# secondboard.net
KiCad netlist of a schematic drawn in EAGLE
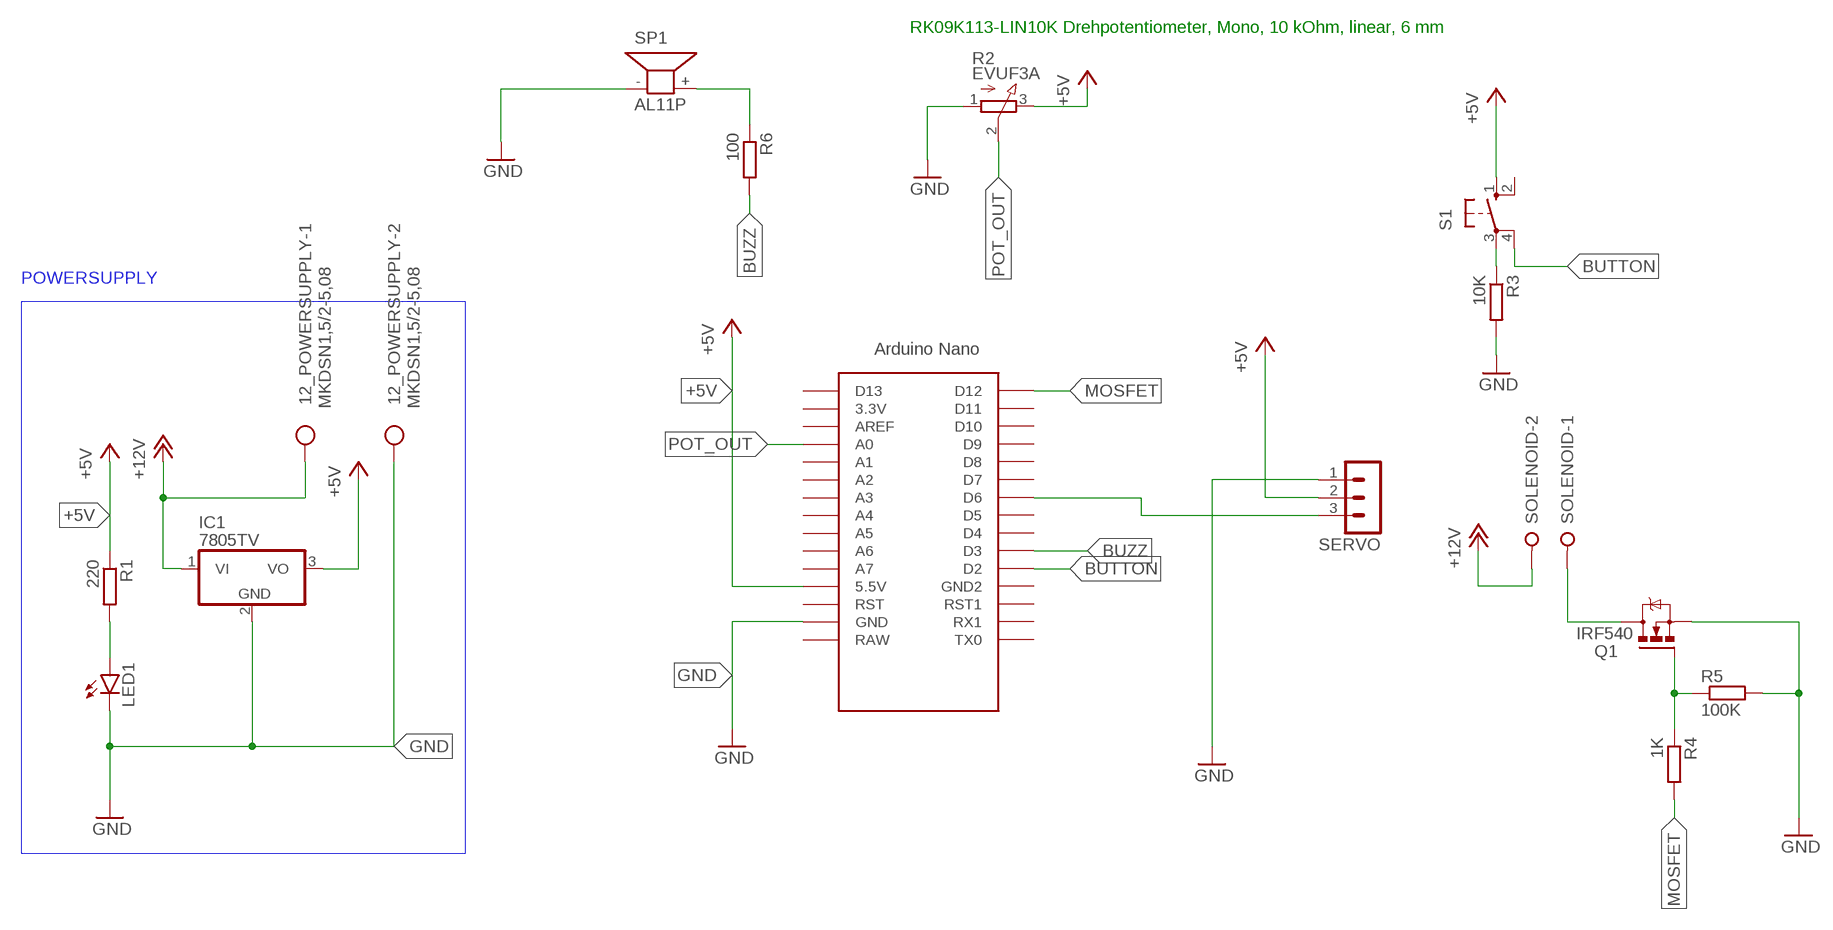
[diagram p0: schematic, sheet 1]

(export (version "E")
  (design (tool "Eeschema 10.0.6"))
  (components
    (comp (ref "12_POWERSUPPLY")
      (value "MKDSN1,5/2-5,08")
      (footprint "eagle-import:MKDSN1,5_2-5,08")
      (libsource (lib "eagle-import") (part "MKDSN1,5/2-5,08"))
    )
    (comp (ref "IC1")
      (value "7805TV")
      (footprint "eagle-import:TO220V")
      (libsource (lib "eagle-import") (part "78TV05"))
    )
    (comp (ref "LED1")
      (value "LED3MM")
      (footprint "eagle-import:LED3MM")
      (libsource (lib "eagle-import") (part "LED3MM"))
    )
    (comp (ref "Q1")
      (value "IRF540")
      (footprint "eagle-import:TO220BV")
      (libsource (lib "eagle-import") (part "IRF540"))
    )
    (comp (ref "R1")
      (value "220")
      (footprint "eagle-import:R0805")
      (libsource (lib "eagle-import") (part "R-EU_R0805"))
    )
    (comp (ref "R2")
      (value "EVUF3A")
      (footprint "eagle-import:EVUF")
      (libsource (lib "eagle-import") (part "EVUAF3"))
    )
    (comp (ref "R3")
      (value "10K")
      (footprint "eagle-import:R0805")
      (libsource (lib "eagle-import") (part "R-EU_R0805"))
    )
    (comp (ref "R4")
      (value "1K")
      (footprint "eagle-import:R0805")
      (libsource (lib "eagle-import") (part "R-EU_R0805"))
    )
    (comp (ref "R5")
      (value "100K")
      (footprint "eagle-import:R0805")
      (libsource (lib "eagle-import") (part "R-EU_R0805"))
    )
    (comp (ref "R6")
      (value "100")
      (footprint "eagle-import:R0805")
      (libsource (lib "eagle-import") (part "R-EU_R0805"))
    )
    (comp (ref "S1")
      (value "10-XX")
      (footprint "eagle-import:B3F-10XX")
      (fields (field (name "MPN") "B3F-1000"))
      (libsource (lib "eagle-import") (part "10-XX"))
    )
    (comp (ref "SERVO")
      (value "MA03-1")
      (footprint "eagle-import:MA03-1")
      (libsource (lib "eagle-import") (part "MA03-1"))
    )
    (comp (ref "SOLENOID")
      (value "W237-02P")
      (footprint "eagle-import:W237-132")
      (libsource (lib "eagle-import") (part "W237-02P"))
    )
    (comp (ref "SP1")
      (value "AL11P")
      (footprint "eagle-import:AL11P")
      (libsource (lib "eagle-import") (part "AL11P"))
    )
    (comp (ref "U$1")
      (value "NANO")
      (footprint "eagle-import:NANO")
      (libsource (lib "eagle-import") (part "NANO"))
    )
  )
  (nets
    (net (code "1") (name "+5V") (class "Default")
      (node (ref "IC1") (pin "3") (pinfunction "VO_3") (pintype "passive"))
      (node (ref "R1") (pin "1") (pinfunction "1_1") (pintype "passive"))
      (node (ref "R2") (pin "3") (pinfunction "E_3") (pintype "passive"))
      (node (ref "S1") (pin "1") (pinfunction "S_1") (pintype "passive"))
      (node (ref "SERVO") (pin "2") (pinfunction "2_2") (pintype "passive"))
      (node (ref "U$1") (pin "5V") (pinfunction "5.5V_5V") (pintype "bidirectional"))
    )
    (net (code "2") (name "+12V") (class "Default")
      (node (ref "12_POWERSUPPLY") (pin "1") (pinfunction "KL_1") (pintype "passive"))
      (node (ref "IC1") (pin "1") (pinfunction "VI_1") (pintype "input"))
      (node (ref "SOLENOID") (pin "2") (pinfunction "KL_2") (pintype "passive"))
    )
    (net (code "3") (name "BUTTON") (class "Default")
      (node (ref "S1") (pin "4") (pinfunction "P1_4") (pintype "passive"))
      (node (ref "U$1") (pin "D2") (pinfunction "D2_D2") (pintype "bidirectional"))
    )
    (net (code "4") (name "BUZZ") (class "Default")
      (node (ref "R6") (pin "2") (pinfunction "2_2") (pintype "passive"))
      (node (ref "U$1") (pin "D3") (pinfunction "D3_D3") (pintype "bidirectional"))
    )
    (net (code "5") (name "GND") (class "Default")
      (node (ref "12_POWERSUPPLY") (pin "2") (pinfunction "KL_2") (pintype "passive"))
      (node (ref "IC1") (pin "2") (pinfunction "GND_2") (pintype "passive"))
      (node (ref "LED1") (pin "K") (pinfunction "C_K") (pintype "passive"))
      (node (ref "Q1") (pin "S") (pinfunction "S_S") (pintype "passive"))
      (node (ref "R2") (pin "1") (pinfunction "A_1") (pintype "passive"))
      (node (ref "R3") (pin "2") (pinfunction "2_2") (pintype "passive"))
      (node (ref "R5") (pin "2") (pinfunction "2_2") (pintype "passive"))
      (node (ref "SERVO") (pin "1") (pinfunction "1_1") (pintype "passive"))
      (node (ref "SP1") (pin "-") (pinfunction "1_-") (pintype "passive"))
      (node (ref "U$1") (pin "GND") (pinfunction "GND_GND") (pintype "bidirectional"))
    )
    (net (code "6") (name "MOSFET") (class "Default")
      (node (ref "R4") (pin "2") (pinfunction "2_2") (pintype "passive"))
      (node (ref "U$1") (pin "D12") (pinfunction "D12_D12") (pintype "bidirectional"))
    )
    (net (code "7") (name "Net-(LED1-PadA)") (class "Default")
      (node (ref "LED1") (pin "A") (pinfunction "A_A") (pintype "passive"))
      (node (ref "R1") (pin "2") (pinfunction "2_2") (pintype "passive"))
    )
    (net (code "8") (name "Net-(Q1-PadG)") (class "Default")
      (node (ref "Q1") (pin "G") (pinfunction "G_G") (pintype "passive"))
      (node (ref "R4") (pin "1") (pinfunction "1_1") (pintype "passive"))
      (node (ref "R5") (pin "1") (pinfunction "1_1") (pintype "passive"))
    )
    (net (code "9") (name "Net-(S1-P)") (class "Default")
      (node (ref "R3") (pin "1") (pinfunction "1_1") (pintype "passive"))
      (node (ref "S1") (pin "3") (pinfunction "P_3") (pintype "passive"))
    )
    (net (code "10") (name "Net-(SERVO-Pad3)") (class "Default")
      (node (ref "SERVO") (pin "3") (pinfunction "3_3") (pintype "passive"))
      (node (ref "U$1") (pin "D6") (pinfunction "D6_D6") (pintype "bidirectional"))
    )
    (net (code "11") (name "Net-(SOLENOIDA-KL)") (class "Default")
      (node (ref "Q1") (pin "D") (pinfunction "D_D") (pintype "passive"))
      (node (ref "SOLENOID") (pin "1") (pinfunction "KL_1") (pintype "passive"))
    )
    (net (code "12") (name "Net-(SP1-2)") (class "Default")
      (node (ref "R6") (pin "1") (pinfunction "1_1") (pintype "passive"))
      (node (ref "SP1") (pin "+") (pinfunction "2_+") (pintype "passive"))
    )
    (net (code "13") (name "POT_OUT") (class "Default")
      (node (ref "R2") (pin "2") (pinfunction "S_2") (pintype "passive"))
      (node (ref "U$1") (pin "A0") (pinfunction "A0_A0") (pintype "bidirectional"))
    )
    (net (code "14") (name "unconnected-(S1-S1-Pad2)") (class "Default")
      (node (ref "S1") (pin "2") (pinfunction "S1_2") (pintype "passive"))
    )
    (net (code "15") (name "unconnected-(U$1-GND2-PadGND1)") (class "Default")
      (node (ref "U$1") (pin "GND1") (pinfunction "GND2_GND1") (pintype "bidirectional"))
    )
    (net (code "16") (name "unconnected-(U$1-Pad3.3V)") (class "Default")
      (node (ref "U$1") (pin "3.3V") (pinfunction "3.3V_3.3V") (pintype "bidirectional"))
    )
    (net (code "17") (name "unconnected-(U$1-PadA1)") (class "Default")
      (node (ref "U$1") (pin "A1") (pinfunction "A1_A1") (pintype "bidirectional"))
    )
    (net (code "18") (name "unconnected-(U$1-PadA2)") (class "Default")
      (node (ref "U$1") (pin "A2") (pinfunction "A2_A2") (pintype "bidirectional"))
    )
    (net (code "19") (name "unconnected-(U$1-PadA3)") (class "Default")
      (node (ref "U$1") (pin "A3") (pinfunction "A3_A3") (pintype "bidirectional"))
    )
    (net (code "20") (name "unconnected-(U$1-PadA4)") (class "Default")
      (node (ref "U$1") (pin "A4") (pinfunction "A4_A4") (pintype "bidirectional"))
    )
    (net (code "21") (name "unconnected-(U$1-PadA5)") (class "Default")
      (node (ref "U$1") (pin "A5") (pinfunction "A5_A5") (pintype "bidirectional"))
    )
    (net (code "22") (name "unconnected-(U$1-PadA6)") (class "Default")
      (node (ref "U$1") (pin "A6") (pinfunction "A6_A6") (pintype "bidirectional"))
    )
    (net (code "23") (name "unconnected-(U$1-PadA7)") (class "Default")
      (node (ref "U$1") (pin "A7") (pinfunction "A7_A7") (pintype "bidirectional"))
    )
    (net (code "24") (name "unconnected-(U$1-PadAREF)") (class "Default")
      (node (ref "U$1") (pin "AREF") (pinfunction "AREF_AREF") (pintype "bidirectional"))
    )
    (net (code "25") (name "unconnected-(U$1-PadD4)") (class "Default")
      (node (ref "U$1") (pin "D4") (pinfunction "D4_D4") (pintype "bidirectional"))
    )
    (net (code "26") (name "unconnected-(U$1-PadD5)") (class "Default")
      (node (ref "U$1") (pin "D5") (pinfunction "D5_D5") (pintype "bidirectional"))
    )
    (net (code "27") (name "unconnected-(U$1-PadD7)") (class "Default")
      (node (ref "U$1") (pin "D7") (pinfunction "D7_D7") (pintype "bidirectional"))
    )
    (net (code "28") (name "unconnected-(U$1-PadD8)") (class "Default")
      (node (ref "U$1") (pin "D8") (pinfunction "D8_D8") (pintype "bidirectional"))
    )
    (net (code "29") (name "unconnected-(U$1-PadD9)") (class "Default")
      (node (ref "U$1") (pin "D9") (pinfunction "D9_D9") (pintype "bidirectional"))
    )
    (net (code "30") (name "unconnected-(U$1-PadD10)") (class "Default")
      (node (ref "U$1") (pin "D10") (pinfunction "D10_D10") (pintype "bidirectional"))
    )
    (net (code "31") (name "unconnected-(U$1-PadD11)") (class "Default")
      (node (ref "U$1") (pin "D11") (pinfunction "D11_D11") (pintype "bidirectional"))
    )
    (net (code "32") (name "unconnected-(U$1-PadD13)") (class "Default")
      (node (ref "U$1") (pin "D13") (pinfunction "D13_D13") (pintype "bidirectional"))
    )
    (net (code "33") (name "unconnected-(U$1-PadICSP1)") (class "Default")
      (node (ref "U$1") (pin "ICSP1") (pinfunction "ICSP1_ICSP1") (pintype "bidirectional"))
    )
    (net (code "34") (name "unconnected-(U$1-PadICSP2)") (class "Default")
      (node (ref "U$1") (pin "ICSP2") (pinfunction "ICSP2_ICSP2") (pintype "bidirectional"))
    )
    (net (code "35") (name "unconnected-(U$1-PadICSP3)") (class "Default")
      (node (ref "U$1") (pin "ICSP3") (pinfunction "ICSP3_ICSP3") (pintype "bidirectional"))
    )
    (net (code "36") (name "unconnected-(U$1-PadICSP4)") (class "Default")
      (node (ref "U$1") (pin "ICSP4") (pinfunction "ICSP4_ICSP4") (pintype "bidirectional"))
    )
    (net (code "37") (name "unconnected-(U$1-PadICSP5)") (class "Default")
      (node (ref "U$1") (pin "ICSP5") (pinfunction "ICSP5_ICSP5") (pintype "bidirectional"))
    )
    (net (code "38") (name "unconnected-(U$1-PadICSP6)") (class "Default")
      (node (ref "U$1") (pin "ICSP6") (pinfunction "ICSP6_ICSP6") (pintype "bidirectional"))
    )
    (net (code "39") (name "unconnected-(U$1-PadRAW)") (class "Default")
      (node (ref "U$1") (pin "RAW") (pinfunction "RAW_RAW") (pintype "bidirectional"))
    )
    (net (code "40") (name "unconnected-(U$1-PadRST)") (class "Default")
      (node (ref "U$1") (pin "RST") (pinfunction "RST_RST") (pintype "bidirectional"))
    )
    (net (code "41") (name "unconnected-(U$1-PadRST1)") (class "Default")
      (node (ref "U$1") (pin "RST1") (pinfunction "RST1_RST1") (pintype "bidirectional"))
    )
    (net (code "42") (name "unconnected-(U$1-PadRX1)") (class "Default")
      (node (ref "U$1") (pin "RX1") (pinfunction "RX1_RX1") (pintype "bidirectional"))
    )
    (net (code "43") (name "unconnected-(U$1-PadTX0)") (class "Default")
      (node (ref "U$1") (pin "TX0") (pinfunction "TX0_TX0") (pintype "bidirectional"))
    )
  )
)
